# BMS-Load_Sharing_Section.net
KiCad netlist of a schematic drawn in Altium Designer
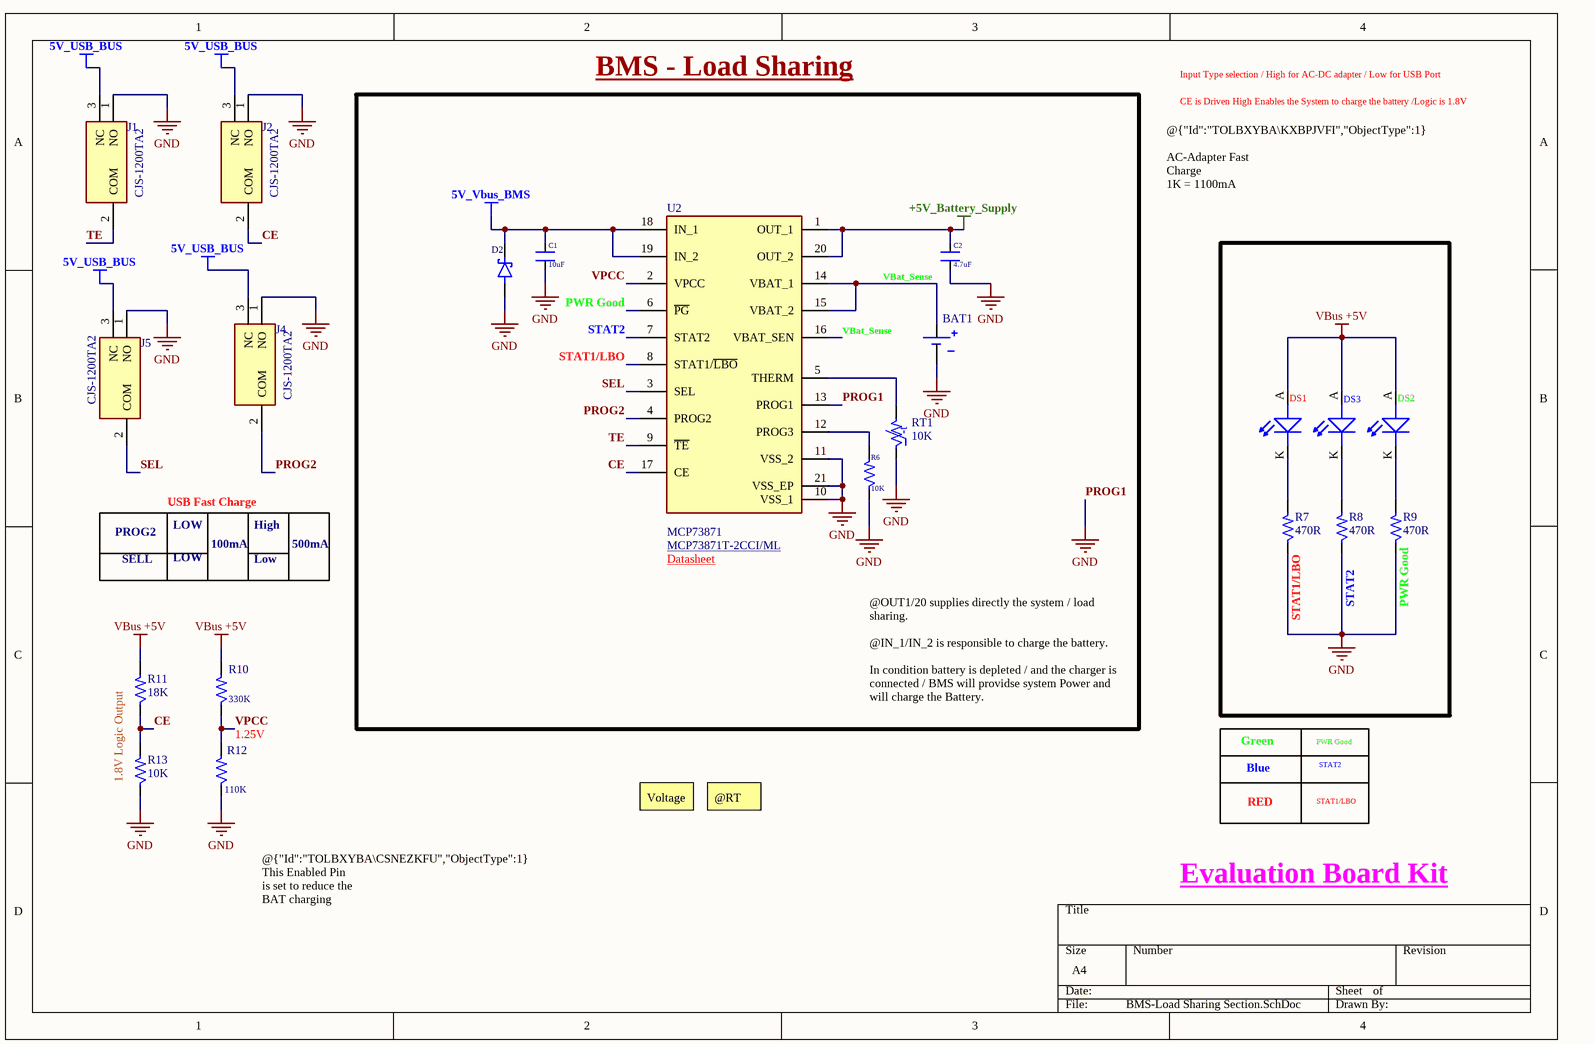
[diagram p0: BMS-Load Sharing Section.SchDoc]

(export (version "E")
  (design (tool "Eeschema 10.0.6"))
  (components
    (comp (ref "BAT1")
      (value "COM-2292")
      (footprint "BAT_761_TH")
      (fields (field (name "MANUFACTURER") "NA"))
      (libsource (lib "Mahdi-SchLib") (part "BAT_787-TH"))
    )
    (comp (ref "C1")
      (value "10uF")
      (footprint "RES_0603")
      (description "Ceramic Capacitor C0G, NP0 0603 (2012 Metric)")
      (fields
        (field (name "MANUFACTURER") "Yageo")
        (field (name "MANUFACTURER PART NUMBER") "600F1R0BT250XT")
      )
      (libsource (lib "NOUMANPCBLIB") (part "CAP_GENERIC_0603_1"))
    )
    (comp (ref "C2")
      (value "4.7uF")
      (footprint "RES_0603")
      (description "Ceramic Capacitor C0G, NP0 0603 (2012 Metric)")
      (fields
        (field (name "MANUFACTURER") "Yageo")
        (field (name "MANUFACTURER PART NUMBER") "600F1R0BT250XT")
      )
      (libsource (lib "NOUMANPCBLIB") (part "CAP_GENERIC_0603_1"))
    )
    (comp (ref "D2")
      (value "~")
      (footprint "SMC (DO-214AB)")
      (description "Diode Schottky 40 V 3A Surface Mount SMC (DO-214AB)")
      (libsource (lib "Mahdi-Library") (part "DIO - Diode Schottky 40 V 3A Surface Mount SMC (DO-214AB)  SS34"))
    )
    (comp (ref "DS1")
      (value "RED")
      (footprint "LED_0805")
      (description "Red 631nm LED Indication - Discrete 2V 0805 (2012 Metric)")
      (fields
        (field (name "MANUFACTURER") "Vishay Lite-On")
        (field (name "MANUFACTURER PART NUMBER") "LTST-C171KRKT")
      )
      (libsource (lib "Mahdi-Library") (part "LED_RED-2V-20mA-0805"))
    )
    (comp (ref "DS2")
      (value "GREEN LED")
      (footprint "LED_0805")
      (description "Green 569nm LED Indication - Discrete 2.1V 0805 (2012 Metric)")
      (fields
        (field (name "MANUFACTURER") "Vishay Lite-On")
        (field (name "MANUFACTURER PART NUMBER") "LTST-C171GKT")
      )
      (libsource (lib "Mahdi-Library") (part "LED_GREEN-2.2-20mA-0805"))
    )
    (comp (ref "DS3")
      (value "BLUE LED")
      (footprint "LED_0805")
      (description "Blue 470nm LED Indication - Discrete 3.3V 0805 (2012 Metric)")
      (fields
        (field (name "MANUFACTURER") "Vishay Lite-On")
        (field (name "MANUFACTURER PART NUMBER") "LTST-C171TBKT")
      )
      (libsource (lib "Mahdi-Library") (part "LED_BLUE-3V3-20mA-0805"))
    )
    (comp (ref "J1")
      (value "CJS-1200TA2")
      (footprint "CJS1200TA2")
      (description "Slide Switches 1 Pole, 2 Contacts, SPDT Top Setting SMD Slide Switch")
      (libsource (lib "Mahdi-Library") (part "Switches Slide 1 Pole, 2 Contacts, SPDT Top Setting SMD Slide Switch"))
    )
    (comp (ref "J2")
      (value "CJS-1200TA2")
      (footprint "CJS1200TA2")
      (description "Slide Switches 1 Pole, 2 Contacts, SPDT Top Setting SMD Slide Switch")
      (libsource (lib "Mahdi-Library") (part "Switches Slide 1 Pole, 2 Contacts, SPDT Top Setting SMD Slide Switch"))
    )
    (comp (ref "J4")
      (value "CJS-1200TA2")
      (footprint "CJS1200TA2")
      (description "Slide Switches 1 Pole, 2 Contacts, SPDT Top Setting SMD Slide Switch")
      (libsource (lib "Mahdi-Library") (part "Switches Slide 1 Pole, 2 Contacts, SPDT Top Setting SMD Slide Switch"))
    )
    (comp (ref "J5")
      (value "CJS-1200TA2")
      (footprint "CJS1200TA2")
      (description "Slide Switches 1 Pole, 2 Contacts, SPDT Top Setting SMD Slide Switch")
      (libsource (lib "Mahdi-Library") (part "Switches Slide 1 Pole, 2 Contacts, SPDT Top Setting SMD Slide Switch"))
    )
    (comp (ref "R6")
      (value "10K")
      (footprint "RES_0603")
      (description "10 kOhms ±1% 0.1W, 1/10W Chip Resistor 0603 (1608 Metric) Automotive AEC-Q200 Thick Film")
      (fields (field (name "MANUFACTURER") "Walsin") (field (name "MANUFACTURER PART NUMBER") "WR06X1002FTL"))
      (libsource (lib "Mahdi-Library") (part "RES_10K-0.1W-1%-0603"))
    )
    (comp (ref "R7")
      (value "470R")
      (footprint "RES_0805")
      (description "470 Ohms ±1% 0.125W, 1/8W Chip Resistor 0805 (2012 Metric) Automotive AEC-Q200 Thick Film")
      (fields (field (name "MANUFACTURER") "Walsin") (field (name "MANUFACTURER PART NUMBER") "WR08X4700FTL"))
      (libsource (lib "Mahdi-Library") (part "RES_470R-0.125W-1%-0805"))
    )
    (comp (ref "R8")
      (value "470R")
      (footprint "RES_0805")
      (description "470 Ohms ±1% 0.125W, 1/8W Chip Resistor 0805 (2012 Metric) Automotive AEC-Q200 Thick Film")
      (fields (field (name "MANUFACTURER") "Walsin") (field (name "MANUFACTURER PART NUMBER") "WR08X4700FTL"))
      (libsource (lib "Mahdi-Library") (part "RES_470R-0.125W-1%-0805"))
    )
    (comp (ref "R9")
      (value "470R")
      (footprint "RES_0805")
      (description "470 Ohms ±1% 0.125W, 1/8W Chip Resistor 0805 (2012 Metric) Automotive AEC-Q200 Thick Film")
      (fields (field (name "MANUFACTURER") "Walsin") (field (name "MANUFACTURER PART NUMBER") "WR08X4700FTL"))
      (libsource (lib "Mahdi-Library") (part "RES_470R-0.125W-1%-0805"))
    )
    (comp (ref "R10")
      (value "330K")
      (footprint "RES_0603")
      (description "10 kOhms ±1% 0.1W, 1/10W Chip Resistor 0603 (1608 Metric) Automotive AEC-Q200 Thick Film")
      (fields (field (name "MANUFACTURER") "Walsin") (field (name "MANUFACTURER PART NUMBER") "WR06X1002FTL"))
      (libsource (lib "NOUMANPCBLIB") (part "RES_10K-0.1W-1%-0603"))
    )
    (comp (ref "R11")
      (value "18K")
      (footprint "RES_0805")
      (description "18 kOhms ±1% 0.125W, 1/8W Chip Resistor 0805 (2012 Metric) Thick Film")
      (fields
        (field (name "MANUFACTURER") "TE Connectivity Passive Product")
        (field (name "MANUFACTURER PART NUMBER") "CRG0805F18K")
      )
      (libsource (lib "Mahdi-Library") (part "RES_18K-0.125W-1%-0805"))
    )
    (comp (ref "R12")
      (value "110K")
      (footprint "RES_0603")
      (description "10 kOhms ±1% 0.1W, 1/10W Chip Resistor 0603 (1608 Metric) Automotive AEC-Q200 Thick Film")
      (fields (field (name "MANUFACTURER") "Walsin") (field (name "MANUFACTURER PART NUMBER") "WR06X1002FTL"))
      (libsource (lib "NOUMANPCBLIB") (part "RES_10K-0.1W-1%-0603"))
    )
    (comp (ref "R13")
      (value "10K")
      (footprint "RES_0603")
      (description "10 kOhms ±1% 0.1W, 1/10W Chip Resistor 0603 (1608 Metric) Automotive AEC-Q200 Thick Film")
      (fields (field (name "MANUFACTURER") "Walsin") (field (name "MANUFACTURER PART NUMBER") "WR06X1002FTL"))
      (libsource (lib "Mahdi-Library") (part "RES_10K-0.1W-1%-0603"))
    )
    (comp (ref "RT1")
      (value "10K")
      (footprint "RES_0805")
      (description "NTC Thermistor 10k 0805 (2012 Metric)")
      (fields
        (field (name "MANUFACTURER") "Vishay BCcomponents")
        (field (name "MANUFACTURER PART NUMBER") "NCP21XV103J03RA")
      )
      (libsource (lib "Mahdi-Library") (part "RT_10K-0805"))
    )
    (comp (ref "U2")
      (value "MCP73871")
      (footprint "QFN50P400X400X100-21N-D")
      (description "Stand-Alone System Load Sharing and Li-Ion/Li-Polymer Battery Charge\r\nManagement Controller")
      (libsource (lib "Mahdi-Library") (part "IC-MCP73871 Battery Management System"))
    )
  )
  (nets
    (net (code "1") (name "+5V_Battery_Supply") (class "Default")
      (node (ref "C2") (pin "2") (pinfunction "2_2") (pintype "passive"))
      (node (ref "U2") (pin "1") (pinfunction "OUT_1_1") (pintype "passive"))
      (node (ref "U2") (pin "20") (pinfunction "OUT_2_20") (pintype "passive"))
    )
    (net (code "2") (name "/CE") (class "Default")
      (node (ref "J2") (pin "2") (pinfunction "COM_2") (pintype "passive"))
      (node (ref "R11") (pin "1") (pinfunction "1_1") (pintype "passive"))
      (node (ref "R13") (pin "2") (pinfunction "2_2") (pintype "passive"))
      (node (ref "U2") (pin "17") (pinfunction "CE_17") (pintype "passive"))
    )
    (net (code "3") (name "/PROG2") (class "Default")
      (node (ref "J4") (pin "2") (pinfunction "COM_2") (pintype "passive"))
      (node (ref "U2") (pin "4") (pinfunction "PROG2_4") (pintype "passive"))
    )
    (net (code "4") (name "/SEL") (class "Default")
      (node (ref "J5") (pin "2") (pinfunction "COM_2") (pintype "passive"))
      (node (ref "U2") (pin "3") (pinfunction "SEL_3") (pintype "passive"))
    )
    (net (code "5") (name "/TE") (class "Default")
      (node (ref "J1") (pin "2") (pinfunction "COM_2") (pintype "passive"))
      (node (ref "U2") (pin "9") (pinfunction "~{TE}_9") (pintype "passive"))
    )
    (net (code "6") (name "/VBat_Sense") (class "Default")
      (node (ref "BAT1") (pin "1") (pinfunction "POS_1") (pintype "passive"))
      (node (ref "U2") (pin "14") (pinfunction "VBAT_1_14") (pintype "passive"))
      (node (ref "U2") (pin "15") (pinfunction "VBAT_2_15") (pintype "passive"))
      (node (ref "U2") (pin "16") (pinfunction "VBAT_SEN_16") (pintype "passive"))
    )
    (net (code "7") (name "/VPCC") (class "Default")
      (node (ref "R10") (pin "1") (pinfunction "1_1") (pintype "passive"))
      (node (ref "R12") (pin "2") (pinfunction "2_2") (pintype "passive"))
      (node (ref "U2") (pin "2") (pinfunction "VPCC_2") (pintype "passive"))
    )
    (net (code "8") (name "5V_USB_BUS") (class "Default")
      (node (ref "J1") (pin "3") (pinfunction "NC_3") (pintype "passive"))
      (node (ref "J2") (pin "3") (pinfunction "NC_3") (pintype "passive"))
      (node (ref "J4") (pin "3") (pinfunction "NC_3") (pintype "passive"))
      (node (ref "J5") (pin "3") (pinfunction "NC_3") (pintype "passive"))
    )
    (net (code "9") (name "5V_Vbus_BMS") (class "Default")
      (node (ref "C1") (pin "2") (pinfunction "2_2") (pintype "passive"))
      (node (ref "D2") (pin "C") (pinfunction "K_C") (pintype "passive"))
      (node (ref "U2") (pin "18") (pinfunction "IN_1_18") (pintype "passive"))
      (node (ref "U2") (pin "19") (pinfunction "IN_2_19") (pintype "passive"))
    )
    (net (code "10") (name "GND") (class "Default")
      (node (ref "BAT1") (pin "2") (pinfunction "NEG_2") (pintype "passive"))
      (node (ref "C1") (pin "1") (pinfunction "1_1") (pintype "passive"))
      (node (ref "C2") (pin "1") (pinfunction "1_1") (pintype "passive"))
      (node (ref "D2") (pin "A") (pinfunction "A_A") (pintype "passive"))
      (node (ref "J1") (pin "1") (pinfunction "NO_1") (pintype "passive"))
      (node (ref "J2") (pin "1") (pinfunction "NO_1") (pintype "passive"))
      (node (ref "J4") (pin "1") (pinfunction "NO_1") (pintype "passive"))
      (node (ref "J5") (pin "1") (pinfunction "NO_1") (pintype "passive"))
      (node (ref "R12") (pin "1") (pinfunction "1_1") (pintype "passive"))
      (node (ref "R13") (pin "1") (pinfunction "1_1") (pintype "passive"))
      (node (ref "R6") (pin "1") (pinfunction "1_1") (pintype "passive"))
      (node (ref "R7") (pin "1") (pinfunction "1_1") (pintype "passive"))
      (node (ref "R8") (pin "1") (pinfunction "1_1") (pintype "passive"))
      (node (ref "R9") (pin "1") (pinfunction "1_1") (pintype "passive"))
      (node (ref "RT1") (pin "1") (pinfunction "1_1") (pintype "passive"))
      (node (ref "U2") (pin "10") (pinfunction "VSS_1_10") (pintype "passive"))
      (node (ref "U2") (pin "11") (pinfunction "VSS_2_11") (pintype "passive"))
      (node (ref "U2") (pin "13") (pinfunction "PROG1_13") (pintype "passive"))
      (node (ref "U2") (pin "21") (pinfunction "VSS_EP_21") (pintype "passive"))
      (node (ref "U2") (pin "6") (pinfunction "~{PG}_6") (pintype "passive"))
      (node (ref "U2") (pin "7") (pinfunction "STAT2_7") (pintype "passive"))
      (node (ref "U2") (pin "8") (pinfunction "STAT1/~{LBO}_8") (pintype "passive"))
    )
    (net (code "11") (name "Net-(DS1-CATHODE)") (class "Default")
      (node (ref "DS1") (pin "K") (pinfunction "CATHODE_K") (pintype "passive"))
      (node (ref "R7") (pin "2") (pinfunction "2_2") (pintype "passive"))
    )
    (net (code "12") (name "Net-(DS2-CATHODE)") (class "Default")
      (node (ref "DS2") (pin "K") (pinfunction "CATHODE_K") (pintype "passive"))
      (node (ref "R9") (pin "2") (pinfunction "2_2") (pintype "passive"))
    )
    (net (code "13") (name "Net-(DS3-CATHODE)") (class "Default")
      (node (ref "DS3") (pin "K") (pinfunction "CATHODE_K") (pintype "passive"))
      (node (ref "R8") (pin "2") (pinfunction "2_2") (pintype "passive"))
    )
    (net (code "14") (name "Net-(U2-PROG3)") (class "Default")
      (node (ref "R6") (pin "2") (pinfunction "2_2") (pintype "passive"))
      (node (ref "U2") (pin "12") (pinfunction "PROG3_12") (pintype "passive"))
    )
    (net (code "15") (name "Net-(U2-THERM)") (class "Default")
      (node (ref "RT1") (pin "2") (pinfunction "2_2") (pintype "passive"))
      (node (ref "U2") (pin "5") (pinfunction "THERM_5") (pintype "passive"))
    )
    (net (code "16") (name "VBus +5V") (class "Default")
      (node (ref "DS1") (pin "A") (pinfunction "ANODE_A") (pintype "passive"))
      (node (ref "DS2") (pin "A") (pinfunction "ANODE_A") (pintype "passive"))
      (node (ref "DS3") (pin "A") (pinfunction "ANODE_A") (pintype "passive"))
      (node (ref "R10") (pin "2") (pinfunction "2_2") (pintype "passive"))
      (node (ref "R11") (pin "2") (pinfunction "2_2") (pintype "passive"))
    )
  )
)
